# RGB_shot.net
KiCad netlist of a schematic drawn in EAGLE
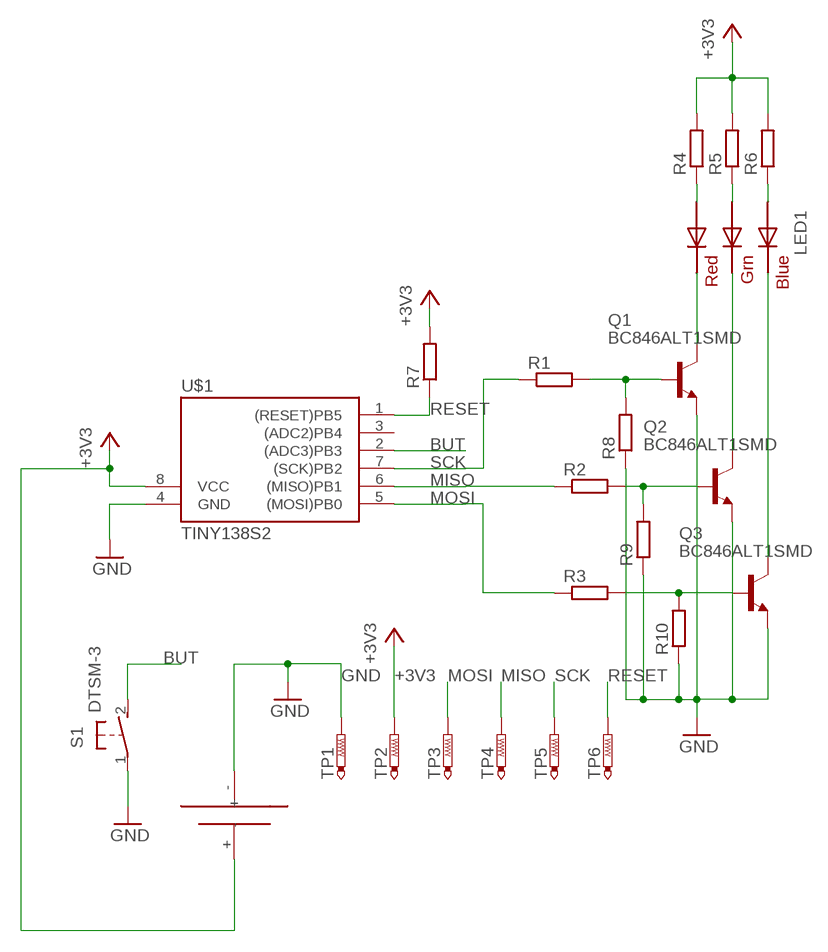
[diagram p0: schematic, sheet 1]

(export (version "E")
  (design (tool "Eeschema 10.0.6"))
  (components
    (comp (ref "LED1")
      (value "RGBLED5050")
      (footprint "eagle-import:RGBLED5050")
      (libsource (lib "eagle-import") (part "RGBLED5050"))
    )
    (comp (ref "Q1")
      (value "BC846ALT1SMD")
      (footprint "eagle-import:SOT23")
      (libsource (lib "eagle-import") (part "BC846SMDALT1"))
    )
    (comp (ref "Q2")
      (value "BC846ALT1SMD")
      (footprint "eagle-import:SOT23")
      (libsource (lib "eagle-import") (part "BC846SMDALT1"))
    )
    (comp (ref "Q3")
      (value "BC846ALT1SMD")
      (footprint "eagle-import:SOT23")
      (libsource (lib "eagle-import") (part "BC846SMDALT1"))
    )
    (comp (ref "R1")
      (value "R-EU_M0805")
      (footprint "eagle-import:M0805")
      (libsource (lib "eagle-import") (part "R-EU_M0805"))
    )
    (comp (ref "R2")
      (value "R-EU_M0805")
      (footprint "eagle-import:M0805")
      (libsource (lib "eagle-import") (part "R-EU_M0805"))
    )
    (comp (ref "R3")
      (value "R-EU_M0805")
      (footprint "eagle-import:M0805")
      (libsource (lib "eagle-import") (part "R-EU_M0805"))
    )
    (comp (ref "R4")
      (value "R-EU_M0805")
      (footprint "eagle-import:M0805")
      (libsource (lib "eagle-import") (part "R-EU_M0805"))
    )
    (comp (ref "R5")
      (value "R-EU_M0805")
      (footprint "eagle-import:M0805")
      (libsource (lib "eagle-import") (part "R-EU_M0805"))
    )
    (comp (ref "R6")
      (value "R-EU_M0805")
      (footprint "eagle-import:M0805")
      (libsource (lib "eagle-import") (part "R-EU_M0805"))
    )
    (comp (ref "R7")
      (value "R-EU_M0805")
      (footprint "eagle-import:M0805")
      (libsource (lib "eagle-import") (part "R-EU_M0805"))
    )
    (comp (ref "R8")
      (value "R-EU_M0805")
      (footprint "eagle-import:M0805")
      (libsource (lib "eagle-import") (part "R-EU_M0805"))
    )
    (comp (ref "R9")
      (value "R-EU_M0805")
      (footprint "eagle-import:M0805")
      (libsource (lib "eagle-import") (part "R-EU_M0805"))
    )
    (comp (ref "R10")
      (value "R-EU_M0805")
      (footprint "eagle-import:M0805")
      (libsource (lib "eagle-import") (part "R-EU_M0805"))
    )
    (comp (ref "S1")
      (value "DTSM-3")
      (footprint "eagle-import:DTSM-3")
      (libsource (lib "eagle-import") (part "DTSM-3"))
    )
    (comp (ref "TP1")
      (value "PTR1TP11R")
      (footprint "eagle-import:TP11R")
      (libsource (lib "eagle-import") (part "PTR1TP11R"))
    )
    (comp (ref "TP2")
      (value "PTR1TP11R")
      (footprint "eagle-import:TP11R")
      (libsource (lib "eagle-import") (part "PTR1TP11R"))
    )
    (comp (ref "TP3")
      (value "PTR1TP11R")
      (footprint "eagle-import:TP11R")
      (libsource (lib "eagle-import") (part "PTR1TP11R"))
    )
    (comp (ref "TP4")
      (value "PTR1TP11R")
      (footprint "eagle-import:TP11R")
      (libsource (lib "eagle-import") (part "PTR1TP11R"))
    )
    (comp (ref "TP5")
      (value "PTR1TP11R")
      (footprint "eagle-import:TP11R")
      (libsource (lib "eagle-import") (part "PTR1TP11R"))
    )
    (comp (ref "TP6")
      (value "PTR1TP11R")
      (footprint "eagle-import:TP11R")
      (libsource (lib "eagle-import") (part "PTR1TP11R"))
    )
    (comp (ref "U$1")
      (value "TINY138S2")
      (footprint "eagle-import:SO08")
      (libsource (lib "eagle-import") (part "TINY138S2"))
    )
    (comp (ref "U$2")
      (value "BAT33_1220")
      (footprint "eagle-import:BAT1220")
      (libsource (lib "eagle-import") (part "BAT33_1220"))
    )
  )
  (nets
    (net (code "1") (name "+3V3") (class "Default")
      (node (ref "R4") (pin "2") (pinfunction "2_2") (pintype "passive"))
      (node (ref "R5") (pin "2") (pinfunction "2_2") (pintype "passive"))
      (node (ref "R6") (pin "2") (pinfunction "2_2") (pintype "passive"))
      (node (ref "R7") (pin "2") (pinfunction "2_2") (pintype "passive"))
      (node (ref "TP2") (pin "TP") (pinfunction "TP_TP") (pintype "input"))
      (node (ref "U$1") (pin "8") (pinfunction "VCC_8") (pintype "power_in"))
      (node (ref "U$2") (pin "+") (pinfunction "+_+") (pintype "passive"))
    )
    (net (code "2") (name "/BUT") (class "Default")
      (node (ref "S1") (pin "2") (pinfunction "2_2") (pintype "passive"))
      (node (ref "U$1") (pin "2") (pinfunction "(ADC3)PB3_2") (pintype "bidirectional"))
    )
    (net (code "3") (name "/MISO") (class "Default")
      (node (ref "R2") (pin "1") (pinfunction "1_1") (pintype "passive"))
      (node (ref "TP4") (pin "TP") (pinfunction "TP_TP") (pintype "input"))
      (node (ref "U$1") (pin "6") (pinfunction "(MISO)PB1_6") (pintype "bidirectional"))
    )
    (net (code "4") (name "/MOSI") (class "Default")
      (node (ref "R3") (pin "1") (pinfunction "1_1") (pintype "passive"))
      (node (ref "TP3") (pin "TP") (pinfunction "TP_TP") (pintype "input"))
      (node (ref "U$1") (pin "5") (pinfunction "(MOSI)PB0_5") (pintype "bidirectional"))
    )
    (net (code "5") (name "/RESET") (class "Default")
      (node (ref "R7") (pin "1") (pinfunction "1_1") (pintype "passive"))
      (node (ref "TP6") (pin "TP") (pinfunction "TP_TP") (pintype "input"))
      (node (ref "U$1") (pin "1") (pinfunction "(RESET)PB5_1") (pintype "bidirectional"))
    )
    (net (code "6") (name "/SCK") (class "Default")
      (node (ref "R1") (pin "1") (pinfunction "1_1") (pintype "passive"))
      (node (ref "TP5") (pin "TP") (pinfunction "TP_TP") (pintype "input"))
      (node (ref "U$1") (pin "7") (pinfunction "(SCK)PB2_7") (pintype "bidirectional"))
    )
    (net (code "7") (name "GND") (class "Default")
      (node (ref "Q1") (pin "2") (pinfunction "E_2") (pintype "passive"))
      (node (ref "Q2") (pin "2") (pinfunction "E_2") (pintype "passive"))
      (node (ref "Q3") (pin "2") (pinfunction "E_2") (pintype "passive"))
      (node (ref "R10") (pin "1") (pinfunction "1_1") (pintype "passive"))
      (node (ref "R8") (pin "1") (pinfunction "1_1") (pintype "passive"))
      (node (ref "R9") (pin "1") (pinfunction "1_1") (pintype "passive"))
      (node (ref "S1") (pin "1") (pinfunction "1_1") (pintype "passive"))
      (node (ref "TP1") (pin "TP") (pinfunction "TP_TP") (pintype "input"))
      (node (ref "U$1") (pin "4") (pinfunction "GND_4") (pintype "power_in"))
      (node (ref "U$2") (pin "-") (pinfunction "-_-") (pintype "passive"))
    )
    (net (code "8") (name "Net-(LED1-BLUE_A)") (class "Default")
      (node (ref "LED1") (pin "3") (pinfunction "BLUE_A_3") (pintype "bidirectional"))
      (node (ref "R6") (pin "1") (pinfunction "1_1") (pintype "passive"))
    )
    (net (code "9") (name "Net-(LED1-BLUE_C)") (class "Default")
      (node (ref "LED1") (pin "4") (pinfunction "BLUE_C_4") (pintype "bidirectional"))
      (node (ref "Q3") (pin "3") (pinfunction "C_3") (pintype "passive"))
    )
    (net (code "10") (name "Net-(LED1-GREEN_A)") (class "Default")
      (node (ref "LED1") (pin "1") (pinfunction "GREEN_A_1") (pintype "bidirectional"))
      (node (ref "R5") (pin "1") (pinfunction "1_1") (pintype "passive"))
    )
    (net (code "11") (name "Net-(LED1-GREEN_C)") (class "Default")
      (node (ref "LED1") (pin "6") (pinfunction "GREEN_C_6") (pintype "bidirectional"))
      (node (ref "Q2") (pin "3") (pinfunction "C_3") (pintype "passive"))
    )
    (net (code "12") (name "Net-(LED1-RED_A)") (class "Default")
      (node (ref "LED1") (pin "2") (pinfunction "RED_A_2") (pintype "bidirectional"))
      (node (ref "R4") (pin "1") (pinfunction "1_1") (pintype "passive"))
    )
    (net (code "13") (name "Net-(LED1-RED_C)") (class "Default")
      (node (ref "LED1") (pin "5") (pinfunction "RED_C_5") (pintype "bidirectional"))
      (node (ref "Q1") (pin "3") (pinfunction "C_3") (pintype "passive"))
    )
    (net (code "14") (name "Net-(Q1-B)") (class "Default")
      (node (ref "Q1") (pin "1") (pinfunction "B_1") (pintype "passive"))
      (node (ref "R1") (pin "2") (pinfunction "2_2") (pintype "passive"))
      (node (ref "R8") (pin "2") (pinfunction "2_2") (pintype "passive"))
    )
    (net (code "15") (name "Net-(Q2-B)") (class "Default")
      (node (ref "Q2") (pin "1") (pinfunction "B_1") (pintype "passive"))
      (node (ref "R2") (pin "2") (pinfunction "2_2") (pintype "passive"))
      (node (ref "R9") (pin "2") (pinfunction "2_2") (pintype "passive"))
    )
    (net (code "16") (name "Net-(Q3-B)") (class "Default")
      (node (ref "Q3") (pin "1") (pinfunction "B_1") (pintype "passive"))
      (node (ref "R10") (pin "2") (pinfunction "2_2") (pintype "passive"))
      (node (ref "R3") (pin "2") (pinfunction "2_2") (pintype "passive"))
    )
    (net (code "17") (name "unconnected-(U$1-(ADC2)PB4-Pad3)") (class "Default")
      (node (ref "U$1") (pin "3") (pinfunction "(ADC2)PB4_3") (pintype "bidirectional"))
    )
  )
)
